# odrb.net
KiCad netlist of a schematic drawn in EAGLE
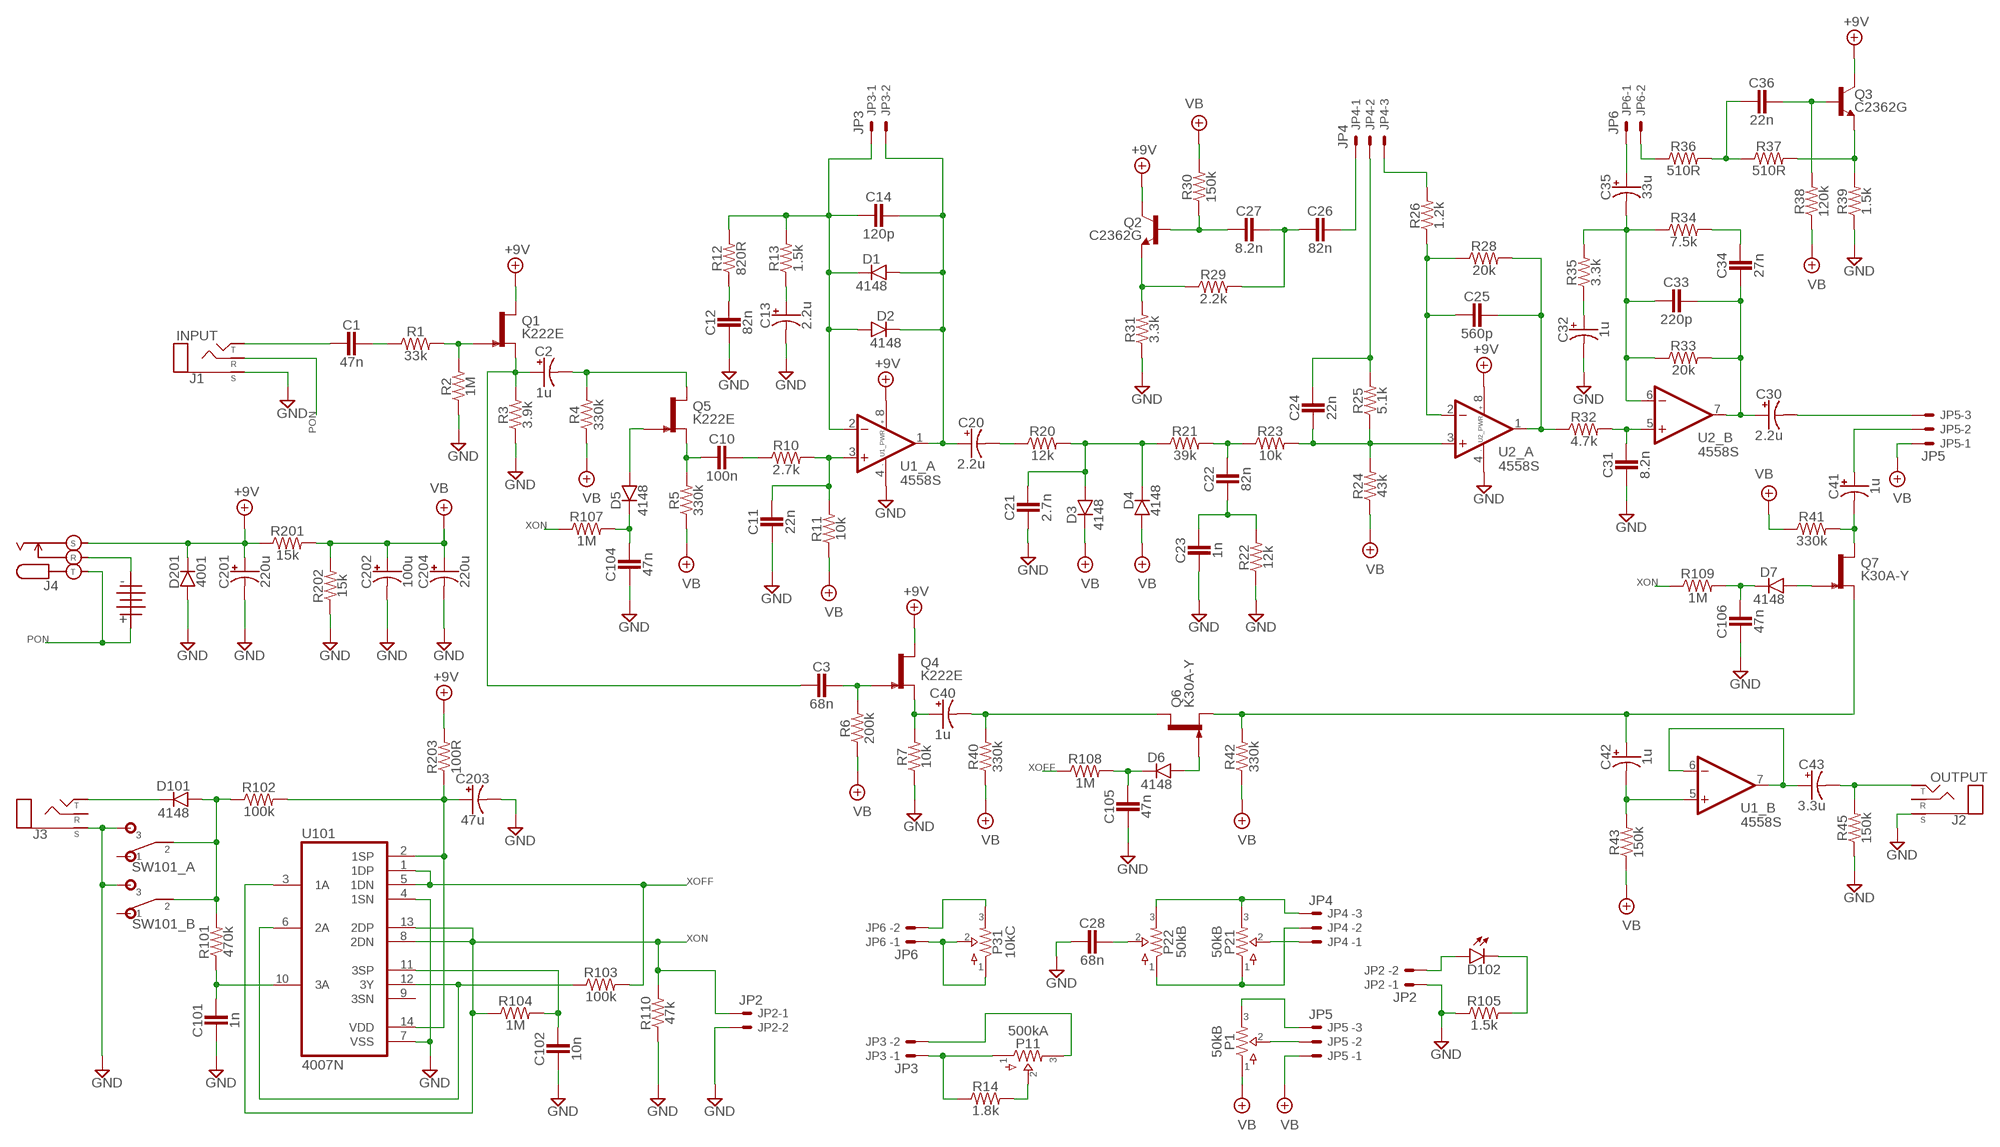
[diagram p0: schematic, sheet 1]

(export (version "E")
  (design (tool "Eeschema 10.0.6"))
  (components
    (comp (ref "1")
      (value "BATTERY")
      (footprint "eagle-import:TWO_PADS")
      (libsource (lib "eagle-import") (part "BATTERY"))
    )
    (comp (ref "C1")
      (value "47n")
      (footprint "eagle-import:BOX_SMALL")
      (libsource (lib "eagle-import") (part "CER/FILMBOX.1"))
    )
    (comp (ref "C2")
      (value "1u")
      (footprint "eagle-import:040_020")
      (libsource (lib "eagle-import") (part "0400"))
    )
    (comp (ref "C3")
      (value "68n")
      (footprint "eagle-import:BOX_SMALL")
      (libsource (lib "eagle-import") (part "CER/FILMBOX.1"))
    )
    (comp (ref "C10")
      (value "100n")
      (footprint "eagle-import:BOX_SMALL")
      (libsource (lib "eagle-import") (part "CER/FILMBOX.1"))
    )
    (comp (ref "C11")
      (value "22n")
      (footprint "eagle-import:BOX_SMALL")
      (libsource (lib "eagle-import") (part "CER/FILMBOX.1"))
    )
    (comp (ref "C12")
      (value "82n")
      (footprint "eagle-import:BOX_SMALL")
      (libsource (lib "eagle-import") (part "CER/FILMBOX.1"))
    )
    (comp (ref "C13")
      (value "2.2u")
      (footprint "eagle-import:040_020")
      (libsource (lib "eagle-import") (part "0400"))
    )
    (comp (ref "C14")
      (value "120p")
      (footprint "eagle-import:BOX_SMALL")
      (libsource (lib "eagle-import") (part "CER/FILMBOX.1"))
    )
    (comp (ref "C20")
      (value "2.2u")
      (footprint "eagle-import:040_020")
      (libsource (lib "eagle-import") (part "0400"))
    )
    (comp (ref "C21")
      (value "2.7n")
      (footprint "eagle-import:BOX_SMALL")
      (libsource (lib "eagle-import") (part "CER/FILMBOX.1"))
    )
    (comp (ref "C22")
      (value "82n")
      (footprint "eagle-import:BOX_SMALL")
      (libsource (lib "eagle-import") (part "CER/FILMBOX.1"))
    )
    (comp (ref "C23")
      (value "1n")
      (footprint "eagle-import:BOX_SMALL")
      (libsource (lib "eagle-import") (part "CER/FILMBOX.1"))
    )
    (comp (ref "C24")
      (value "22n")
      (footprint "eagle-import:BOX_SMALL")
      (libsource (lib "eagle-import") (part "CER/FILMBOX.1"))
    )
    (comp (ref "C25")
      (value "560p")
      (footprint "eagle-import:BOX_SMALL")
      (libsource (lib "eagle-import") (part "CER/FILMBOX.1"))
    )
    (comp (ref "C26")
      (value "82n")
      (footprint "eagle-import:BOX_SMALL")
      (libsource (lib "eagle-import") (part "CER/FILMBOX.1"))
    )
    (comp (ref "C27")
      (value "8.2n")
      (footprint "eagle-import:BOX_SMALL")
      (libsource (lib "eagle-import") (part "CER/FILMBOX.1"))
    )
    (comp (ref "C28")
      (value "68n")
      (footprint "eagle-import:BOX_SMALL")
      (libsource (lib "eagle-import") (part "CER/FILMBOX.1"))
    )
    (comp (ref "C30")
      (value "2.2u")
      (footprint "eagle-import:040_020")
      (libsource (lib "eagle-import") (part "0400"))
    )
    (comp (ref "C31")
      (value "8.2n")
      (footprint "eagle-import:BOX_SMALL")
      (libsource (lib "eagle-import") (part "CER/FILMBOX.1"))
    )
    (comp (ref "C32")
      (value "1u")
      (footprint "eagle-import:040_020")
      (libsource (lib "eagle-import") (part "0400"))
    )
    (comp (ref "C33")
      (value "220p")
      (footprint "eagle-import:BOX_SMALL")
      (libsource (lib "eagle-import") (part "CER/FILMBOX.1"))
    )
    (comp (ref "C34")
      (value "27n")
      (footprint "eagle-import:BOX_SMALL")
      (libsource (lib "eagle-import") (part "CER/FILMBOX.1"))
    )
    (comp (ref "C35")
      (value "33u")
      (footprint "eagle-import:040_020")
      (libsource (lib "eagle-import") (part "0400"))
    )
    (comp (ref "C36")
      (value "22n")
      (footprint "eagle-import:BOX_SMALL")
      (libsource (lib "eagle-import") (part "CER/FILMBOX.1"))
    )
    (comp (ref "C40")
      (value "1u")
      (footprint "eagle-import:040_020")
      (libsource (lib "eagle-import") (part "0400"))
    )
    (comp (ref "C41")
      (value "1u")
      (footprint "eagle-import:040_020")
      (libsource (lib "eagle-import") (part "0400"))
    )
    (comp (ref "C42")
      (value "1u")
      (footprint "eagle-import:040_020")
      (libsource (lib "eagle-import") (part "0400"))
    )
    (comp (ref "C43")
      (value "3.3u")
      (footprint "eagle-import:040_020")
      (libsource (lib "eagle-import") (part "0400"))
    )
    (comp (ref "C101")
      (value "1n")
      (footprint "eagle-import:BOX_SMALL")
      (libsource (lib "eagle-import") (part "CER/FILMBOX.1"))
    )
    (comp (ref "C102")
      (value "10n")
      (footprint "eagle-import:BOX_SMALL")
      (libsource (lib "eagle-import") (part "CER/FILMBOX.1"))
    )
    (comp (ref "C104")
      (value "47n")
      (footprint "eagle-import:BOX_SMALL")
      (libsource (lib "eagle-import") (part "CER/FILMBOX.1"))
    )
    (comp (ref "C105")
      (value "47n")
      (footprint "eagle-import:BOX_SMALL")
      (libsource (lib "eagle-import") (part "CER/FILMBOX.1"))
    )
    (comp (ref "C106")
      (value "47n")
      (footprint "eagle-import:BOX_SMALL")
      (libsource (lib "eagle-import") (part "CER/FILMBOX.1"))
    )
    (comp (ref "C201")
      (value "220u")
      (footprint "eagle-import:040_020")
      (libsource (lib "eagle-import") (part "0400"))
    )
    (comp (ref "C202")
      (value "100u")
      (footprint "eagle-import:040_020")
      (libsource (lib "eagle-import") (part "0400"))
    )
    (comp (ref "C203")
      (value "47u")
      (footprint "eagle-import:040_020")
      (libsource (lib "eagle-import") (part "0400"))
    )
    (comp (ref "C204")
      (value "220u")
      (footprint "eagle-import:040_020")
      (libsource (lib "eagle-import") (part "0400"))
    )
    (comp (ref "D1")
      (value "4148")
      (footprint "eagle-import:DO35-2")
      (libsource (lib "eagle-import") (part "DO35.2"))
    )
    (comp (ref "D2")
      (value "4148")
      (footprint "eagle-import:DO35-2")
      (libsource (lib "eagle-import") (part "DO35.2"))
    )
    (comp (ref "D3")
      (value "4148")
      (footprint "eagle-import:DO35-2")
      (libsource (lib "eagle-import") (part "DO35.2"))
    )
    (comp (ref "D4")
      (value "4148")
      (footprint "eagle-import:DO35-2")
      (libsource (lib "eagle-import") (part "DO35.2"))
    )
    (comp (ref "D5")
      (value "4148")
      (footprint "eagle-import:DO35-2")
      (libsource (lib "eagle-import") (part "DO35.2"))
    )
    (comp (ref "D6")
      (value "4148")
      (footprint "eagle-import:DO35-2")
      (libsource (lib "eagle-import") (part "DO35.2"))
    )
    (comp (ref "D7")
      (value "4148")
      (footprint "eagle-import:DO35-2")
      (libsource (lib "eagle-import") (part "DO35.2"))
    )
    (comp (ref "D101")
      (value "4148")
      (footprint "eagle-import:DO35-2")
      (libsource (lib "eagle-import") (part "DO35.2"))
    )
    (comp (ref "D102")
      (value "LED")
      (footprint "eagle-import:3MM_D")
      (libsource (lib "eagle-import") (part "LED"))
    )
    (comp (ref "D201")
      (value "4001")
      (footprint "eagle-import:DO35-2")
      (libsource (lib "eagle-import") (part "DO35.2"))
    )
    (comp (ref "J1")
      (value "INPUT")
      (footprint "eagle-import:THREEPADS")
      (libsource (lib "eagle-import") (part "STEREO3PADS"))
    )
    (comp (ref "J2")
      (value "OUTPUT")
      (footprint "eagle-import:THREEPADS")
      (libsource (lib "eagle-import") (part "STEREO3PADS"))
    )
    (comp (ref "J3")
      (value "STEREO3PADS")
      (footprint "eagle-import:THREEPADS")
      (libsource (lib "eagle-import") (part "STEREO3PADS"))
    )
    (comp (ref "J4")
      (value "POWER")
      (footprint "eagle-import:DC_KOBICONN")
      (libsource (lib "eagle-import") (part "DC_KOBICONN"))
    )
    (comp (ref "JP2")
      (value "JP2")
      (footprint "eagle-import:JST-XH-02-PACKAGE-LONG-PAD")
      (libsource (lib "eagle-import") (part "JST-XH-02-PIN-LONG-PAD"))
    )
    (comp (ref "JP2 ")
      (value "JP2")
      (footprint "eagle-import:JST-XH-02-PACKAGE-LONG-PAD")
      (libsource (lib "eagle-import") (part "JST-XH-02-PIN-LONG-PAD"))
    )
    (comp (ref "JP3")
      (value "JP3")
      (footprint "eagle-import:JST-XH-02-PACKAGE-LONG-PAD")
      (libsource (lib "eagle-import") (part "JST-XH-02-PIN-LONG-PAD"))
    )
    (comp (ref "JP3 ")
      (value "JP3")
      (footprint "eagle-import:JST-XH-02-PACKAGE-LONG-PAD")
      (libsource (lib "eagle-import") (part "JST-XH-02-PIN-LONG-PAD"))
    )
    (comp (ref "JP4")
      (value "JP4")
      (footprint "eagle-import:JST-XH-03-PACKAGE-LONG-PAD")
      (libsource (lib "eagle-import") (part "JST-XH-03-PIN-LONG-PAD"))
    )
    (comp (ref "JP4 ")
      (value "JP4")
      (footprint "eagle-import:JST-XH-03-PACKAGE-LONG-PAD")
      (libsource (lib "eagle-import") (part "JST-XH-03-PIN-LONG-PAD"))
    )
    (comp (ref "JP5")
      (value "JP5")
      (footprint "eagle-import:JST-XH-03-PACKAGE-LONG-PAD")
      (libsource (lib "eagle-import") (part "JST-XH-03-PIN-LONG-PAD"))
    )
    (comp (ref "JP5 ")
      (value "JP5")
      (footprint "eagle-import:JST-XH-03-PACKAGE-LONG-PAD")
      (libsource (lib "eagle-import") (part "JST-XH-03-PIN-LONG-PAD"))
    )
    (comp (ref "JP6")
      (value "JP6")
      (footprint "eagle-import:JST-XH-02-PACKAGE-LONG-PAD")
      (libsource (lib "eagle-import") (part "JST-XH-02-PIN-LONG-PAD"))
    )
    (comp (ref "JP6 ")
      (value "JP6")
      (footprint "eagle-import:JST-XH-02-PACKAGE-LONG-PAD")
      (libsource (lib "eagle-import") (part "JST-XH-02-PIN-LONG-PAD"))
    )
    (comp (ref "P1")
      (value "50kB")
      (footprint "eagle-import:16MM")
      (libsource (lib "eagle-import") (part "POTS16MM"))
    )
    (comp (ref "P11")
      (value "500kA")
      (footprint "eagle-import:16MM")
      (libsource (lib "eagle-import") (part "POTS16MM"))
    )
    (comp (ref "P21")
      (value "50kB")
      (footprint "eagle-import:16MM")
      (libsource (lib "eagle-import") (part "POTS16MM"))
    )
    (comp (ref "P22")
      (value "50kB")
      (footprint "eagle-import:16MM")
      (libsource (lib "eagle-import") (part "POTS16MM"))
    )
    (comp (ref "P31")
      (value "10kC")
      (footprint "eagle-import:16MM")
      (libsource (lib "eagle-import") (part "POTS16MM"))
    )
    (comp (ref "Q1")
      (value "K222E")
      (footprint "eagle-import:TO92-")
      (libsource (lib "eagle-import") (part "2N3819TO-92S"))
    )
    (comp (ref "Q2")
      (value "C2362G")
      (footprint "eagle-import:TO92-")
      (libsource (lib "eagle-import") (part "2N3904"))
    )
    (comp (ref "Q3")
      (value "C2362G")
      (footprint "eagle-import:TO92-")
      (libsource (lib "eagle-import") (part "2N3904"))
    )
    (comp (ref "Q4")
      (value "K222E")
      (footprint "eagle-import:TO92-")
      (libsource (lib "eagle-import") (part "2N3819TO-92S"))
    )
    (comp (ref "Q5")
      (value "K222E")
      (footprint "eagle-import:TO92-")
      (libsource (lib "eagle-import") (part "2N3819TO-92S"))
    )
    (comp (ref "Q6")
      (value "K30A-Y")
      (footprint "eagle-import:TO92-")
      (libsource (lib "eagle-import") (part "2N3819TO-92S"))
    )
    (comp (ref "Q7")
      (value "K30A-Y")
      (footprint "eagle-import:TO92-")
      (libsource (lib "eagle-import") (part "2N3819TO-92S"))
    )
    (comp (ref "R1")
      (value "33k")
      (footprint "eagle-import:R0207_3")
      (libsource (lib "eagle-import") (part "R_.3B"))
    )
    (comp (ref "R2")
      (value "1M")
      (footprint "eagle-import:R0207_3")
      (libsource (lib "eagle-import") (part "R_.3B"))
    )
    (comp (ref "R3")
      (value "3.9k")
      (footprint "eagle-import:R0207_3")
      (libsource (lib "eagle-import") (part "R_.3B"))
    )
    (comp (ref "R4")
      (value "330k")
      (footprint "eagle-import:R0207_3")
      (libsource (lib "eagle-import") (part "R_.3B"))
    )
    (comp (ref "R5")
      (value "330k")
      (footprint "eagle-import:R0207_3")
      (libsource (lib "eagle-import") (part "R_.3B"))
    )
    (comp (ref "R6")
      (value "200k")
      (footprint "eagle-import:R0207_3")
      (libsource (lib "eagle-import") (part "R_.3B"))
    )
    (comp (ref "R7")
      (value "10k")
      (footprint "eagle-import:R0207_3")
      (libsource (lib "eagle-import") (part "R_.3B"))
    )
    (comp (ref "R10")
      (value "2.7k")
      (footprint "eagle-import:R0207_3")
      (libsource (lib "eagle-import") (part "R_.3B"))
    )
    (comp (ref "R11")
      (value "10k")
      (footprint "eagle-import:R0207_3")
      (libsource (lib "eagle-import") (part "R_.3B"))
    )
    (comp (ref "R12")
      (value "820R")
      (footprint "eagle-import:R0207_3")
      (libsource (lib "eagle-import") (part "R_.3B"))
    )
    (comp (ref "R13")
      (value "1.5k")
      (footprint "eagle-import:R0207_3")
      (libsource (lib "eagle-import") (part "R_.3B"))
    )
    (comp (ref "R14")
      (value "1.8k")
      (footprint "eagle-import:R0207_3")
      (libsource (lib "eagle-import") (part "R_.3B"))
    )
    (comp (ref "R20")
      (value "12k")
      (footprint "eagle-import:R0207_3")
      (libsource (lib "eagle-import") (part "R_.3B"))
    )
    (comp (ref "R21")
      (value "39k")
      (footprint "eagle-import:R0207_3")
      (libsource (lib "eagle-import") (part "R_.3B"))
    )
    (comp (ref "R22")
      (value "12k")
      (footprint "eagle-import:R0207_3")
      (libsource (lib "eagle-import") (part "R_.3B"))
    )
    (comp (ref "R23")
      (value "10k")
      (footprint "eagle-import:R0207_3")
      (libsource (lib "eagle-import") (part "R_.3B"))
    )
    (comp (ref "R24")
      (value "43k")
      (footprint "eagle-import:R0207_3")
      (libsource (lib "eagle-import") (part "R_.3B"))
    )
    (comp (ref "R25")
      (value "5.1k")
      (footprint "eagle-import:R0207_3")
      (libsource (lib "eagle-import") (part "R_.3B"))
    )
    (comp (ref "R26")
      (value "1.2k")
      (footprint "eagle-import:R0207_3")
      (libsource (lib "eagle-import") (part "R_.3B"))
    )
    (comp (ref "R28")
      (value "20k")
      (footprint "eagle-import:R0207_3")
      (libsource (lib "eagle-import") (part "R_.3B"))
    )
    (comp (ref "R29")
      (value "2.2k")
      (footprint "eagle-import:R0207_3")
      (libsource (lib "eagle-import") (part "R_.3B"))
    )
    (comp (ref "R30")
      (value "150k")
      (footprint "eagle-import:R0207_3")
      (libsource (lib "eagle-import") (part "R_.3B"))
    )
    (comp (ref "R31")
      (value "3.3k")
      (footprint "eagle-import:R0207_3")
      (libsource (lib "eagle-import") (part "R_.3B"))
    )
    (comp (ref "R32")
      (value "4.7k")
      (footprint "eagle-import:R0207_3")
      (libsource (lib "eagle-import") (part "R_.3B"))
    )
    (comp (ref "R33")
      (value "20k")
      (footprint "eagle-import:R0207_3")
      (libsource (lib "eagle-import") (part "R_.3B"))
    )
    (comp (ref "R34")
      (value "7.5k")
      (footprint "eagle-import:R0207_3")
      (libsource (lib "eagle-import") (part "R_.3B"))
    )
    (comp (ref "R35")
      (value "3.3k")
      (footprint "eagle-import:R0207_3")
      (libsource (lib "eagle-import") (part "R_.3B"))
    )
    (comp (ref "R36")
      (value "510R")
      (footprint "eagle-import:R0207_3")
      (libsource (lib "eagle-import") (part "R_.3B"))
    )
    (comp (ref "R37")
      (value "510R")
      (footprint "eagle-import:R0207_3")
      (libsource (lib "eagle-import") (part "R_.3B"))
    )
    (comp (ref "R38")
      (value "120k")
      (footprint "eagle-import:R0207_3")
      (libsource (lib "eagle-import") (part "R_.3B"))
    )
    (comp (ref "R39")
      (value "1.5k")
      (footprint "eagle-import:R0207_3")
      (libsource (lib "eagle-import") (part "R_.3B"))
    )
    (comp (ref "R40")
      (value "330k")
      (footprint "eagle-import:R0207_3")
      (libsource (lib "eagle-import") (part "R_.3B"))
    )
    (comp (ref "R41")
      (value "330k")
      (footprint "eagle-import:R0207_3")
      (libsource (lib "eagle-import") (part "R_.3B"))
    )
    (comp (ref "R42")
      (value "330k")
      (footprint "eagle-import:R0207_3")
      (libsource (lib "eagle-import") (part "R_.3B"))
    )
    (comp (ref "R43")
      (value "150k")
      (footprint "eagle-import:R0207_3")
      (libsource (lib "eagle-import") (part "R_.3B"))
    )
    (comp (ref "R45")
      (value "150k")
      (footprint "eagle-import:R0207_3")
      (libsource (lib "eagle-import") (part "R_.3B"))
    )
    (comp (ref "R101")
      (value "470k")
      (footprint "eagle-import:R0207_3")
      (libsource (lib "eagle-import") (part "R_.3B"))
    )
    (comp (ref "R102")
      (value "100k")
      (footprint "eagle-import:R0207_3")
      (libsource (lib "eagle-import") (part "R_.3B"))
    )
    (comp (ref "R103")
      (value "100k")
      (footprint "eagle-import:R0207_3")
      (libsource (lib "eagle-import") (part "R_.3B"))
    )
    (comp (ref "R104")
      (value "1M")
      (footprint "eagle-import:R0207_3")
      (libsource (lib "eagle-import") (part "R_.3B"))
    )
    (comp (ref "R105")
      (value "1.5k")
      (footprint "eagle-import:R0207_3")
      (libsource (lib "eagle-import") (part "R_.3B"))
    )
    (comp (ref "R107")
      (value "1M")
      (footprint "eagle-import:R0207_3")
      (libsource (lib "eagle-import") (part "R_.3B"))
    )
    (comp (ref "R108")
      (value "1M")
      (footprint "eagle-import:R0207_3")
      (libsource (lib "eagle-import") (part "R_.3B"))
    )
    (comp (ref "R109")
      (value "1M")
      (footprint "eagle-import:R0207_3")
      (libsource (lib "eagle-import") (part "R_.3B"))
    )
    (comp (ref "R110")
      (value "47k")
      (footprint "eagle-import:R0207_3")
      (libsource (lib "eagle-import") (part "R_.3B"))
    )
    (comp (ref "R201")
      (value "15k")
      (footprint "eagle-import:R0207_3")
      (libsource (lib "eagle-import") (part "R_.3B"))
    )
    (comp (ref "R202")
      (value "15k")
      (footprint "eagle-import:R0207_3")
      (libsource (lib "eagle-import") (part "R_.3B"))
    )
    (comp (ref "R203")
      (value "100R")
      (footprint "eagle-import:R0207_3")
      (libsource (lib "eagle-import") (part "R_.3B"))
    )
    (comp (ref "SW101")
      (value "DPDT")
      (footprint "eagle-import:DPDT")
      (libsource (lib "eagle-import") (part "DPDT"))
    )
    (comp (ref "U1")
      (value "4558S")
      (footprint "eagle-import:DIL0")
      (libsource (lib "eagle-import") (part "DUALTH"))
    )
    (comp (ref "U2")
      (value "4558S")
      (footprint "eagle-import:DIL0")
      (libsource (lib "eagle-import") (part "DUALTH"))
    )
    (comp (ref "U101")
      (value "4007N")
      (footprint "eagle-import:DIL14")
      (libsource (lib "eagle-import") (part "4007N"))
    )
  )
  (nets
    (net (code "1") (name "+9V") (class "Default")
      (node (ref "C201") (pin "+") (pinfunction "+_+") (pintype "passive"))
      (node (ref "D201") (pin "C") (pinfunction "C_C") (pintype "passive"))
      (node (ref "J4") (pin "S") (pinfunction "S_S") (pintype "bidirectional"))
      (node (ref "Q1") (pin "3") (pinfunction "D_3") (pintype "passive"))
      (node (ref "Q2") (pin "1") (pinfunction "C_1") (pintype "passive"))
      (node (ref "Q3") (pin "1") (pinfunction "C_1") (pintype "passive"))
      (node (ref "Q4") (pin "3") (pinfunction "D_3") (pintype "passive"))
      (node (ref "R201") (pin "1") (pinfunction "1_1") (pintype "passive"))
      (node (ref "R203") (pin "2") (pinfunction "2_2") (pintype "passive"))
      (node (ref "U1") (pin "8") (pinfunction "V+_8") (pintype "power_in"))
      (node (ref "U2") (pin "8") (pinfunction "V+_8") (pintype "power_in"))
    )
    (net (code "2") (name "/PON") (class "Default")
      (node (ref "1") (pin "T") (pinfunction "P$1_T") (pintype "bidirectional"))
      (node (ref "J1") (pin "RING") (pinfunction "R_RING") (pintype "passive"))
      (node (ref "J4") (pin "T") (pinfunction "T_T") (pintype "bidirectional"))
    )
    (net (code "3") (name "/XOFF") (class "Default")
      (node (ref "R103") (pin "2") (pinfunction "2_2") (pintype "passive"))
      (node (ref "R108") (pin "1") (pinfunction "1_1") (pintype "passive"))
      (node (ref "U101") (pin "1") (pinfunction "1DP_1") (pintype "open_collector"))
      (node (ref "U101") (pin "5") (pinfunction "1DN_5") (pintype "open_collector"))
    )
    (net (code "4") (name "/XON") (class "Default")
      (node (ref "JP2") (pin "1") (pinfunction "S_1") (pintype "passive"))
      (node (ref "R104") (pin "1") (pinfunction "1_1") (pintype "passive"))
      (node (ref "R107") (pin "1") (pinfunction "1_1") (pintype "passive"))
      (node (ref "R109") (pin "1") (pinfunction "1_1") (pintype "passive"))
      (node (ref "R110") (pin "2") (pinfunction "2_2") (pintype "passive"))
      (node (ref "U101") (pin "13") (pinfunction "2DP_13") (pintype "bidirectional"))
      (node (ref "U101") (pin "3") (pinfunction "1A_3") (pintype "input"))
      (node (ref "U101") (pin "8") (pinfunction "2DN_8") (pintype "bidirectional"))
    )
    (net (code "5") (name "GND") (class "Default")
      (node (ref "C101") (pin "2") (pinfunction "2_2") (pintype "passive"))
      (node (ref "C102") (pin "2") (pinfunction "2_2") (pintype "passive"))
      (node (ref "C104") (pin "2") (pinfunction "2_2") (pintype "passive"))
      (node (ref "C105") (pin "2") (pinfunction "2_2") (pintype "passive"))
      (node (ref "C106") (pin "2") (pinfunction "2_2") (pintype "passive"))
      (node (ref "C11") (pin "2") (pinfunction "2_2") (pintype "passive"))
      (node (ref "C12") (pin "2") (pinfunction "2_2") (pintype "passive"))
      (node (ref "C13") (pin "-") (pinfunction "-_-") (pintype "passive"))
      (node (ref "C201") (pin "-") (pinfunction "-_-") (pintype "passive"))
      (node (ref "C202") (pin "-") (pinfunction "-_-") (pintype "passive"))
      (node (ref "C203") (pin "-") (pinfunction "-_-") (pintype "passive"))
      (node (ref "C204") (pin "-") (pinfunction "-_-") (pintype "passive"))
      (node (ref "C21") (pin "2") (pinfunction "2_2") (pintype "passive"))
      (node (ref "C23") (pin "2") (pinfunction "2_2") (pintype "passive"))
      (node (ref "C28") (pin "2") (pinfunction "2_2") (pintype "passive"))
      (node (ref "C31") (pin "2") (pinfunction "2_2") (pintype "passive"))
      (node (ref "C32") (pin "-") (pinfunction "-_-") (pintype "passive"))
      (node (ref "D201") (pin "A") (pinfunction "A_A") (pintype "passive"))
      (node (ref "J1") (pin "SLEEVE") (pinfunction "S_SLEEVE") (pintype "passive"))
      (node (ref "J2") (pin "SLEEVE") (pinfunction "S_SLEEVE") (pintype "passive"))
      (node (ref "J3") (pin "SLEEVE") (pinfunction "S_SLEEVE") (pintype "passive"))
      (node (ref "JP2") (pin "2") (pinfunction "S_2") (pintype "passive"))
      (node (ref "JP2 ") (pin "1") (pinfunction "S_1") (pintype "passive"))
      (node (ref "R105") (pin "1") (pinfunction "1_1") (pintype "passive"))
      (node (ref "R110") (pin "1") (pinfunction "1_1") (pintype "passive"))
      (node (ref "R2") (pin "1") (pinfunction "1_1") (pintype "passive"))
      (node (ref "R202") (pin "1") (pinfunction "1_1") (pintype "passive"))
      (node (ref "R22") (pin "1") (pinfunction "1_1") (pintype "passive"))
      (node (ref "R3") (pin "1") (pinfunction "1_1") (pintype "passive"))
      (node (ref "R31") (pin "1") (pinfunction "1_1") (pintype "passive"))
      (node (ref "R39") (pin "1") (pinfunction "1_1") (pintype "passive"))
      (node (ref "R45") (pin "1") (pinfunction "1_1") (pintype "passive"))
      (node (ref "R7") (pin "1") (pinfunction "1_1") (pintype "passive"))
      (node (ref "SW101") (pin "A3") (pinfunction "3_A3") (pintype "passive"))
      (node (ref "SW101") (pin "B3") (pinfunction "3_B3") (pintype "passive"))
      (node (ref "U1") (pin "4") (pinfunction "V-_4") (pintype "power_in"))
      (node (ref "U101") (pin "4") (pinfunction "1SN_4") (pintype "open_collector"))
      (node (ref "U101") (pin "7") (pinfunction "VSS_7") (pintype "input"))
      (node (ref "U2") (pin "4") (pinfunction "V-_4") (pintype "power_in"))
    )
    (net (code "6") (name "Net-(1-P$2)") (class "Default")
      (node (ref "1") (pin "S") (pinfunction "P$2_S") (pintype "bidirectional"))
      (node (ref "J4") (pin "R") (pinfunction "R_R") (pintype "bidirectional"))
    )
    (net (code "7") (name "Net-(C1-Pad1)") (class "Default")
      (node (ref "C1") (pin "1") (pinfunction "1_1") (pintype "passive"))
      (node (ref "R1") (pin "1") (pinfunction "1_1") (pintype "passive"))
    )
    (net (code "8") (name "Net-(C10-Pad1)") (class "Default")
      (node (ref "C10") (pin "1") (pinfunction "1_1") (pintype "passive"))
      (node (ref "R10") (pin "1") (pinfunction "1_1") (pintype "passive"))
    )
    (net (code "9") (name "Net-(C12-Pad1)") (class "Default")
      (node (ref "C12") (pin "1") (pinfunction "1_1") (pintype "passive"))
      (node (ref "R12") (pin "1") (pinfunction "1_1") (pintype "passive"))
    )
    (net (code "10") (name "Net-(C13-Pad+)") (class "Default")
      (node (ref "C13") (pin "+") (pinfunction "+_+") (pintype "passive"))
      (node (ref "R13") (pin "1") (pinfunction "1_1") (pintype "passive"))
    )
    (net (code "11") (name "Net-(C20-Pad-)") (class "Default")
      (node (ref "C20") (pin "-") (pinfunction "-_-") (pintype "passive"))
      (node (ref "R20") (pin "1") (pinfunction "1_1") (pintype "passive"))
    )
    (net (code "12") (name "Net-(C21-Pad1)") (class "Default")
      (node (ref "C21") (pin "1") (pinfunction "1_1") (pintype "passive"))
      (node (ref "D3") (pin "A") (pinfunction "A_A") (pintype "passive"))
      (node (ref "D4") (pin "C") (pinfunction "C_C") (pintype "passive"))
      (node (ref "R20") (pin "2") (pinfunction "2_2") (pintype "passive"))
      (node (ref "R21") (pin "1") (pinfunction "1_1") (pintype "passive"))
    )
    (net (code "13") (name "Net-(C22-Pad1)") (class "Default")
      (node (ref "C22") (pin "1") (pinfunction "1_1") (pintype "passive"))
      (node (ref "R21") (pin "2") (pinfunction "2_2") (pintype "passive"))
      (node (ref "R23") (pin "1") (pinfunction "1_1") (pintype "passive"))
    )
    (net (code "14") (name "Net-(C22-Pad2)") (class "Default")
      (node (ref "C22") (pin "2") (pinfunction "2_2") (pintype "passive"))
      (node (ref "C23") (pin "1") (pinfunction "1_1") (pintype "passive"))
      (node (ref "R22") (pin "2") (pinfunction "2_2") (pintype "passive"))
    )
    (net (code "15") (name "Net-(C26-Pad2)") (class "Default")
      (node (ref "C26") (pin "2") (pinfunction "2_2") (pintype "passive"))
      (node (ref "C27") (pin "1") (pinfunction "1_1") (pintype "passive"))
      (node (ref "R29") (pin "2") (pinfunction "2_2") (pintype "passive"))
    )
    (net (code "16") (name "Net-(C28-Pad1)") (class "Default")
      (node (ref "C28") (pin "1") (pinfunction "1_1") (pintype "passive"))
      (node (ref "P22") (pin "2") (pinfunction "2_2") (pintype "passive"))
    )
    (net (code "17") (name "Net-(C32-Pad+)") (class "Default")
      (node (ref "C32") (pin "+") (pinfunction "+_+") (pintype "passive"))
      (node (ref "R35") (pin "1") (pinfunction "1_1") (pintype "passive"))
    )
    (net (code "18") (name "Net-(C34-Pad1)") (class "Default")
      (node (ref "C34") (pin "1") (pinfunction "1_1") (pintype "passive"))
      (node (ref "R34") (pin "2") (pinfunction "2_2") (pintype "passive"))
    )
    (net (code "19") (name "Net-(C36-Pad2)") (class "Default")
      (node (ref "C36") (pin "2") (pinfunction "2_2") (pintype "passive"))
      (node (ref "R36") (pin "2") (pinfunction "2_2") (pintype "passive"))
      (node (ref "R37") (pin "1") (pinfunction "1_1") (pintype "passive"))
    )
    (net (code "20") (name "Net-(C104-Pad1)") (class "Default")
      (node (ref "C104") (pin "1") (pinfunction "1_1") (pintype "passive"))
      (node (ref "D5") (pin "C") (pinfunction "C_C") (pintype "passive"))
      (node (ref "R107") (pin "2") (pinfunction "2_2") (pintype "passive"))
    )
    (net (code "21") (name "Net-(C105-Pad1)") (class "Default")
      (node (ref "C105") (pin "1") (pinfunction "1_1") (pintype "passive"))
      (node (ref "D6") (pin "C") (pinfunction "C_C") (pintype "passive"))
      (node (ref "R108") (pin "2") (pinfunction "2_2") (pintype "passive"))
    )
    (net (code "22") (name "Net-(C106-Pad1)") (class "Default")
      (node (ref "C106") (pin "1") (pinfunction "1_1") (pintype "passive"))
      (node (ref "D7") (pin "C") (pinfunction "C_C") (pintype "passive"))
      (node (ref "R109") (pin "2") (pinfunction "2_2") (pintype "passive"))
    )
    (net (code "23") (name "Net-(D102-A)") (class "Default")
      (node (ref "D102") (pin "ANODE") (pinfunction "A_ANODE") (pintype "passive"))
      (node (ref "JP2 ") (pin "2") (pinfunction "S_2") (pintype "passive"))
    )
    (net (code "24") (name "Net-(D102-C)") (class "Default")
      (node (ref "D102") (pin "P$1") (pinfunction "C_P$1") (pintype "passive"))
      (node (ref "R105") (pin "2") (pinfunction "2_2") (pintype "passive"))
    )
    (net (code "25") (name "Net-(J1-T)") (class "Default")
      (node (ref "C1") (pin "2") (pinfunction "2_2") (pintype "passive"))
      (node (ref "J1") (pin "TIP") (pinfunction "T_TIP") (pintype "passive"))
    )
    (net (code "26") (name "Net-(J2-T)") (class "Default")
      (node (ref "C43") (pin "-") (pinfunction "-_-") (pintype "passive"))
      (node (ref "J2") (pin "TIP") (pinfunction "T_TIP") (pintype "passive"))
      (node (ref "R45") (pin "2") (pinfunction "2_2") (pintype "passive"))
    )
    (net (code "27") (name "Net-(J3-T)") (class "Default")
      (node (ref "D101") (pin "C") (pinfunction "C_C") (pintype "passive"))
      (node (ref "J3") (pin "TIP") (pinfunction "T_TIP") (pintype "passive"))
    )
    (net (code "28") (name "Net-(JP3A-S)") (class "Default")
      (node (ref "C14") (pin "2") (pinfunction "2_2") (pintype "passive"))
      (node (ref "D1") (pin "C") (pinfunction "C_C") (pintype "passive"))
      (node (ref "D2") (pin "A") (pinfunction "A_A") (pintype "passive"))
      (node (ref "JP3") (pin "1") (pinfunction "S_1") (pintype "passive"))
      (node (ref "R12") (pin "2") (pinfunction "2_2") (pintype "passive"))
      (node (ref "R13") (pin "2") (pinfunction "2_2") (pintype "passive"))
      (node (ref "U1") (pin "2") (pinfunction "-IN_2") (pintype "input"))
    )
    (net (code "29") (name "Net-(JP3B-S)") (class "Default")
      (node (ref "C14") (pin "1") (pinfunction "1_1") (pintype "passive"))
      (node (ref "C20") (pin "+") (pinfunction "+_+") (pintype "passive"))
      (node (ref "D1") (pin "A") (pinfunction "A_A") (pintype "passive"))
      (node (ref "D2") (pin "C") (pinfunction "C_C") (pintype "passive"))
      (node (ref "JP3") (pin "2") (pinfunction "S_2") (pintype "passive"))
      (node (ref "U1") (pin "1") (pinfunction "OUT_1") (pintype "output"))
    )
    (net (code "30") (name "Net-(JP3 A-S)") (class "Default")
      (node (ref "JP3 ") (pin "1") (pinfunction "S_1") (pintype "passive"))
      (node (ref "P11") (pin "1") (pinfunction "1_1") (pintype "passive"))
      (node (ref "R14") (pin "1") (pinfunction "1_1") (pintype "passive"))
    )
    (net (code "31") (name "Net-(JP3 B-S)") (class "Default")
      (node (ref "JP3 ") (pin "2") (pinfunction "S_2") (pintype "passive"))
      (node (ref "P11") (pin "3") (pinfunction "3_3") (pintype "passive"))
    )
    (net (code "32") (name "Net-(JP4A-S)") (class "Default")
      (node (ref "C26") (pin "1") (pinfunction "1_1") (pintype "passive"))
      (node (ref "JP4") (pin "1") (pinfunction "S_1") (pintype "passive"))
    )
    (net (code "33") (name "Net-(JP4B-S)") (class "Default")
      (node (ref "C24") (pin "1") (pinfunction "1_1") (pintype "passive"))
      (node (ref "JP4") (pin "2") (pinfunction "S_2") (pintype "passive"))
      (node (ref "R25") (pin "2") (pinfunction "2_2") (pintype "passive"))
    )
    (net (code "34") (name "Net-(JP4C-S)") (class "Default")
      (node (ref "JP4") (pin "3") (pinfunction "S_3") (pintype "passive"))
      (node (ref "R26") (pin "2") (pinfunction "2_2") (pintype "passive"))
    )
    (net (code "35") (name "Net-(JP4 A-S)") (class "Default")
      (node (ref "JP4 ") (pin "1") (pinfunction "S_1") (pintype "passive"))
      (node (ref "P21") (pin "2") (pinfunction "2_2") (pintype "passive"))
    )
    (net (code "36") (name "Net-(JP4 B-S)") (class "Default")
      (node (ref "JP4 ") (pin "2") (pinfunction "S_2") (pintype "passive"))
      (node (ref "P21") (pin "1") (pinfunction "1_1") (pintype "passive"))
      (node (ref "P22") (pin "1") (pinfunction "1_1") (pintype "passive"))
    )
    (net (code "37") (name "Net-(JP4 C-S)") (class "Default")
      (node (ref "JP4 ") (pin "3") (pinfunction "S_3") (pintype "passive"))
      (node (ref "P21") (pin "3") (pinfunction "3_3") (pintype "passive"))
      (node (ref "P22") (pin "3") (pinfunction "3_3") (pintype "passive"))
    )
    (net (code "38") (name "Net-(JP5B-S)") (class "Default")
      (node (ref "C41") (pin "+") (pinfunction "+_+") (pintype "passive"))
      (node (ref "JP5") (pin "2") (pinfunction "S_2") (pintype "passive"))
    )
    (net (code "39") (name "Net-(JP5C-S)") (class "Default")
      (node (ref "C30") (pin "-") (pinfunction "-_-") (pintype "passive"))
      (node (ref "JP5") (pin "3") (pinfunction "S_3") (pintype "passive"))
    )
    (net (code "40") (name "Net-(JP5 B-S)") (class "Default")
      (node (ref "JP5 ") (pin "2") (pinfunction "S_2") (pintype "passive"))
      (node (ref "P1") (pin "2") (pinfunction "2_2") (pintype "passive"))
    )
    (net (code "41") (name "Net-(JP5 C-S)") (class "Default")
      (node (ref "JP5 ") (pin "3") (pinfunction "S_3") (pintype "passive"))
      (node (ref "P1") (pin "3") (pinfunction "3_3") (pintype "passive"))
    )
    (net (code "42") (name "Net-(JP6A-S)") (class "Default")
      (node (ref "C35") (pin "+") (pinfunction "+_+") (pintype "passive"))
      (node (ref "JP6") (pin "1") (pinfunction "S_1") (pintype "passive"))
    )
    (net (code "43") (name "Net-(JP6B-S)") (class "Default")
      (node (ref "JP6") (pin "2") (pinfunction "S_2") (pintype "passive"))
      (node (ref "R36") (pin "1") (pinfunction "1_1") (pintype "passive"))
    )
    (net (code "44") (name "Net-(JP6 A-S)") (class "Default")
      (node (ref "JP6 ") (pin "1") (pinfunction "S_1") (pintype "passive"))
      (node (ref "P31") (pin "1") (pinfunction "1_1") (pintype "passive"))
      (node (ref "P31") (pin "2") (pinfunction "2_2") (pintype "passive"))
    )
    (net (code "45") (name "Net-(JP6 B-S)") (class "Default")
      (node (ref "JP6 ") (pin "2") (pinfunction "S_2") (pintype "passive"))
      (node (ref "P31") (pin "3") (pinfunction "3_3") (pintype "passive"))
    )
    (net (code "46") (name "Net-(P11-Pad2)") (class "Default")
      (node (ref "P11") (pin "2") (pinfunction "2_2") (pintype "passive"))
      (node (ref "R14") (pin "2") (pinfunction "2_2") (pintype "passive"))
    )
    (net (code "47") (name "Net-(Q1-G)") (class "Default")
      (node (ref "Q1") (pin "2") (pinfunction "G_2") (pintype "passive"))
      (node (ref "R1") (pin "2") (pinfunction "2_2") (pintype "passive"))
      (node (ref "R2") (pin "2") (pinfunction "2_2") (pintype "passive"))
    )
    (net (code "48") (name "Net-(Q1-S)") (class "Default")
      (node (ref "C2") (pin "+") (pinfunction "+_+") (pintype "passive"))
      (node (ref "C3") (pin "2") (pinfunction "2_2") (pintype "passive"))
      (node (ref "Q1") (pin "1") (pinfunction "S_1") (pintype "passive"))
      (node (ref "R3") (pin "2") (pinfunction "2_2") (pintype "passive"))
    )
    (net (code "49") (name "Net-(Q2-B)") (class "Default")
      (node (ref "C27") (pin "2") (pinfunction "2_2") (pintype "passive"))
      (node (ref "Q2") (pin "2") (pinfunction "B_2") (pintype "passive"))
      (node (ref "R30") (pin "1") (pinfunction "1_1") (pintype "passive"))
    )
    (net (code "50") (name "Net-(Q2-E)") (class "Default")
      (node (ref "Q2") (pin "3") (pinfunction "E_3") (pintype "passive"))
      (node (ref "R29") (pin "1") (pinfunction "1_1") (pintype "passive"))
      (node (ref "R31") (pin "2") (pinfunction "2_2") (pintype "passive"))
    )
    (net (code "51") (name "Net-(Q3-B)") (class "Default")
      (node (ref "C36") (pin "1") (pinfunction "1_1") (pintype "passive"))
      (node (ref "Q3") (pin "2") (pinfunction "B_2") (pintype "passive"))
      (node (ref "R38") (pin "2") (pinfunction "2_2") (pintype "passive"))
    )
    (net (code "52") (name "Net-(Q3-E)") (class "Default")
      (node (ref "Q3") (pin "3") (pinfunction "E_3") (pintype "passive"))
      (node (ref "R37") (pin "2") (pinfunction "2_2") (pintype "passive"))
      (node (ref "R39") (pin "2") (pinfunction "2_2") (pintype "passive"))
    )
    (net (code "53") (name "Net-(Q4-G)") (class "Default")
      (node (ref "C3") (pin "1") (pinfunction "1_1") (pintype "passive"))
      (node (ref "Q4") (pin "2") (pinfunction "G_2") (pintype "passive"))
      (node (ref "R6") (pin "2") (pinfunction "2_2") (pintype "passive"))
    )
    (net (code "54") (name "Net-(Q4-S)") (class "Default")
      (node (ref "C40") (pin "+") (pinfunction "+_+") (pintype "passive"))
      (node (ref "Q4") (pin "1") (pinfunction "S_1") (pintype "passive"))
      (node (ref "R7") (pin "2") (pinfunction "2_2") (pintype "passive"))
    )
    (net (code "55") (name "Net-(Q5-D)") (class "Default")
      (node (ref "C2") (pin "-") (pinfunction "-_-") (pintype "passive"))
      (node (ref "Q5") (pin "3") (pinfunction "D_3") (pintype "passive"))
      (node (ref "R4") (pin "2") (pinfunction "2_2") (pintype "passive"))
    )
    (net (code "56") (name "Net-(Q5-G)") (class "Default")
      (node (ref "D5") (pin "A") (pinfunction "A_A") (pintype "passive"))
      (node (ref "Q5") (pin "2") (pinfunction "G_2") (pintype "passive"))
    )
    (net (code "57") (name "Net-(Q5-S)") (class "Default")
      (node (ref "C10") (pin "2") (pinfunction "2_2") (pintype "passive"))
      (node (ref "Q5") (pin "1") (pinfunction "S_1") (pintype "passive"))
      (node (ref "R5") (pin "2") (pinfunction "2_2") (pintype "passive"))
    )
    (net (code "58") (name "Net-(Q6-D)") (class "Default")
      (node (ref "C40") (pin "-") (pinfunction "-_-") (pintype "passive"))
      (node (ref "Q6") (pin "3") (pinfunction "D_3") (pintype "passive"))
      (node (ref "R40") (pin "2") (pinfunction "2_2") (pintype "passive"))
    )
    (net (code "59") (name "Net-(Q6-G)") (class "Default")
      (node (ref "D6") (pin "A") (pinfunction "A_A") (pintype "passive"))
      (node (ref "Q6") (pin "2") (pinfunction "G_2") (pintype "passive"))
    )
    (net (code "60") (name "Net-(Q6-S)") (class "Default")
      (node (ref "C42") (pin "+") (pinfunction "+_+") (pintype "passive"))
      (node (ref "Q6") (pin "1") (pinfunction "S_1") (pintype "passive"))
      (node (ref "Q7") (pin "1") (pinfunction "S_1") (pintype "passive"))
      (node (ref "R42") (pin "2") (pinfunction "2_2") (pintype "passive"))
    )
    (net (code "61") (name "Net-(Q7-D)") (class "Default")
      (node (ref "C41") (pin "-") (pinfunction "-_-") (pintype "passive"))
      (node (ref "Q7") (pin "3") (pinfunction "D_3") (pintype "passive"))
      (node (ref "R41") (pin "2") (pinfunction "2_2") (pintype "passive"))
    )
    (net (code "62") (name "Net-(Q7-G)") (class "Default")
      (node (ref "D7") (pin "A") (pinfunction "A_A") (pintype "passive"))
      (node (ref "Q7") (pin "2") (pinfunction "G_2") (pintype "passive"))
    )
    (net (code "63") (name "Net-(SW101A-2)") (class "Default")
      (node (ref "D101") (pin "A") (pinfunction "A_A") (pintype "passive"))
      (node (ref "R101") (pin "2") (pinfunction "2_2") (pintype "passive"))
      (node (ref "R102") (pin "1") (pinfunction "1_1") (pintype "passive"))
      (node (ref "SW101") (pin "A2") (pinfunction "2_A2") (pintype "passive"))
      (node (ref "SW101") (pin "B2") (pinfunction "2_B2") (pintype "passive"))
    )
    (net (code "64") (name "Net-(U1A-+IN)") (class "Default")
      (node (ref "C11") (pin "1") (pinfunction "1_1") (pintype "passive"))
      (node (ref "R10") (pin "2") (pinfunction "2_2") (pintype "passive"))
      (node (ref "R11") (pin "2") (pinfunction "2_2") (pintype "passive"))
      (node (ref "U1") (pin "3") (pinfunction "+IN_3") (pintype "input"))
    )
    (net (code "65") (name "Net-(U1B-+IN)") (class "Default")
      (node (ref "C42") (pin "-") (pinfunction "-_-") (pintype "passive"))
      (node (ref "R43") (pin "2") (pinfunction "2_2") (pintype "passive"))
      (node (ref "U1") (pin "5") (pinfunction "+IN_5") (pintype "input"))
    )
    (net (code "66") (name "Net-(U1B--IN)") (class "Default")
      (node (ref "C43") (pin "+") (pinfunction "+_+") (pintype "passive"))
      (node (ref "U1") (pin "6") (pinfunction "-IN_6") (pintype "input"))
      (node (ref "U1") (pin "7") (pinfunction "OUT_7") (pintype "output"))
    )
    (net (code "67") (name "Net-(U2A-+IN)") (class "Default")
      (node (ref "C24") (pin "2") (pinfunction "2_2") (pintype "passive"))
      (node (ref "R23") (pin "2") (pinfunction "2_2") (pintype "passive"))
      (node (ref "R24") (pin "2") (pinfunction "2_2") (pintype "passive"))
      (node (ref "R25") (pin "1") (pinfunction "1_1") (pintype "passive"))
      (node (ref "U2") (pin "3") (pinfunction "+IN_3") (pintype "input"))
    )
    (net (code "68") (name "Net-(U2A--IN)") (class "Default")
      (node (ref "C25") (pin "2") (pinfunction "2_2") (pintype "passive"))
      (node (ref "R26") (pin "1") (pinfunction "1_1") (pintype "passive"))
      (node (ref "R28") (pin "1") (pinfunction "1_1") (pintype "passive"))
      (node (ref "U2") (pin "2") (pinfunction "-IN_2") (pintype "input"))
    )
    (net (code "69") (name "Net-(U2A-OUT)") (class "Default")
      (node (ref "C25") (pin "1") (pinfunction "1_1") (pintype "passive"))
      (node (ref "R28") (pin "2") (pinfunction "2_2") (pintype "passive"))
      (node (ref "R32") (pin "1") (pinfunction "1_1") (pintype "passive"))
      (node (ref "U2") (pin "1") (pinfunction "OUT_1") (pintype "output"))
    )
    (net (code "70") (name "Net-(U2B-+IN)") (class "Default")
      (node (ref "C31") (pin "1") (pinfunction "1_1") (pintype "passive"))
      (node (ref "R32") (pin "2") (pinfunction "2_2") (pintype "passive"))
      (node (ref "U2") (pin "5") (pinfunction "+IN_5") (pintype "input"))
    )
    (net (code "71") (name "Net-(U2B--IN)") (class "Default")
      (node (ref "C33") (pin "2") (pinfunction "2_2") (pintype "passive"))
      (node (ref "C35") (pin "-") (pinfunction "-_-") (pintype "passive"))
      (node (ref "R33") (pin "1") (pinfunction "1_1") (pintype "passive"))
      (node (ref "R34") (pin "1") (pinfunction "1_1") (pintype "passive"))
      (node (ref "R35") (pin "2") (pinfunction "2_2") (pintype "passive"))
      (node (ref "U2") (pin "6") (pinfunction "-IN_6") (pintype "input"))
    )
    (net (code "72") (name "Net-(U2B-OUT)") (class "Default")
      (node (ref "C30") (pin "+") (pinfunction "+_+") (pintype "passive"))
      (node (ref "C33") (pin "1") (pinfunction "1_1") (pintype "passive"))
      (node (ref "C34") (pin "2") (pinfunction "2_2") (pintype "passive"))
      (node (ref "R33") (pin "2") (pinfunction "2_2") (pintype "passive"))
      (node (ref "U2") (pin "7") (pinfunction "OUT_7") (pintype "output"))
    )
    (net (code "73") (name "Net-(U101-1SP)") (class "Default")
      (node (ref "C203") (pin "+") (pinfunction "+_+") (pintype "passive"))
      (node (ref "R102") (pin "2") (pinfunction "2_2") (pintype "passive"))
      (node (ref "R203") (pin "1") (pinfunction "1_1") (pintype "passive"))
      (node (ref "U101") (pin "14") (pinfunction "VDD_14") (pintype "input"))
      (node (ref "U101") (pin "2") (pinfunction "1SP_2") (pintype "open_collector"))
    )
    (net (code "74") (name "Net-(U101-2A)") (class "Default")
      (node (ref "R103") (pin "1") (pinfunction "1_1") (pintype "passive"))
      (node (ref "U101") (pin "12") (pinfunction "3Y_12") (pintype "bidirectional"))
      (node (ref "U101") (pin "6") (pinfunction "2A_6") (pintype "input"))
    )
    (net (code "75") (name "Net-(U101-3A)") (class "Default")
      (node (ref "C101") (pin "1") (pinfunction "1_1") (pintype "passive"))
      (node (ref "R101") (pin "1") (pinfunction "1_1") (pintype "passive"))
      (node (ref "U101") (pin "10") (pinfunction "3A_10") (pintype "input"))
    )
    (net (code "76") (name "Net-(U101-3SP)") (class "Default")
      (node (ref "C102") (pin "1") (pinfunction "1_1") (pintype "passive"))
      (node (ref "R104") (pin "2") (pinfunction "2_2") (pintype "passive"))
      (node (ref "U101") (pin "11") (pinfunction "3SP_11") (pintype "bidirectional"))
    )
    (net (code "77") (name "VB") (class "Default")
      (node (ref "C202") (pin "+") (pinfunction "+_+") (pintype "passive"))
      (node (ref "C204") (pin "+") (pinfunction "+_+") (pintype "passive"))
      (node (ref "D3") (pin "C") (pinfunction "C_C") (pintype "passive"))
      (node (ref "D4") (pin "A") (pinfunction "A_A") (pintype "passive"))
      (node (ref "JP5") (pin "1") (pinfunction "S_1") (pintype "passive"))
      (node (ref "JP5 ") (pin "1") (pinfunction "S_1") (pintype "passive"))
      (node (ref "P1") (pin "1") (pinfunction "1_1") (pintype "passive"))
      (node (ref "R11") (pin "1") (pinfunction "1_1") (pintype "passive"))
      (node (ref "R201") (pin "2") (pinfunction "2_2") (pintype "passive"))
      (node (ref "R202") (pin "2") (pinfunction "2_2") (pintype "passive"))
      (node (ref "R24") (pin "1") (pinfunction "1_1") (pintype "passive"))
      (node (ref "R30") (pin "2") (pinfunction "2_2") (pintype "passive"))
      (node (ref "R38") (pin "1") (pinfunction "1_1") (pintype "passive"))
      (node (ref "R4") (pin "1") (pinfunction "1_1") (pintype "passive"))
      (node (ref "R40") (pin "1") (pinfunction "1_1") (pintype "passive"))
      (node (ref "R41") (pin "1") (pinfunction "1_1") (pintype "passive"))
      (node (ref "R42") (pin "1") (pinfunction "1_1") (pintype "passive"))
      (node (ref "R43") (pin "1") (pinfunction "1_1") (pintype "passive"))
      (node (ref "R5") (pin "1") (pinfunction "1_1") (pintype "passive"))
      (node (ref "R6") (pin "1") (pinfunction "1_1") (pintype "passive"))
    )
    (net (code "78") (name "unconnected-(J2-R-PadRING)") (class "Default")
      (node (ref "J2") (pin "RING") (pinfunction "R_RING") (pintype "passive"))
    )
    (net (code "79") (name "unconnected-(J3-R-PadRING)") (class "Default")
      (node (ref "J3") (pin "RING") (pinfunction "R_RING") (pintype "passive"))
    )
    (net (code "80") (name "unconnected-(SW101A-1-PadA1)") (class "Default")
      (node (ref "SW101") (pin "A1") (pinfunction "1_A1") (pintype "passive"))
    )
    (net (code "81") (name "unconnected-(SW101B-1-PadB1)") (class "Default")
      (node (ref "SW101") (pin "B1") (pinfunction "1_B1") (pintype "passive"))
    )
    (net (code "82") (name "unconnected-(U101-3SN-Pad9)") (class "Default")
      (node (ref "U101") (pin "9") (pinfunction "3SN_9") (pintype "bidirectional"))
    )
  )
)
